# picoKey_230408.net
KiCad netlist of a schematic drawn in EAGLE
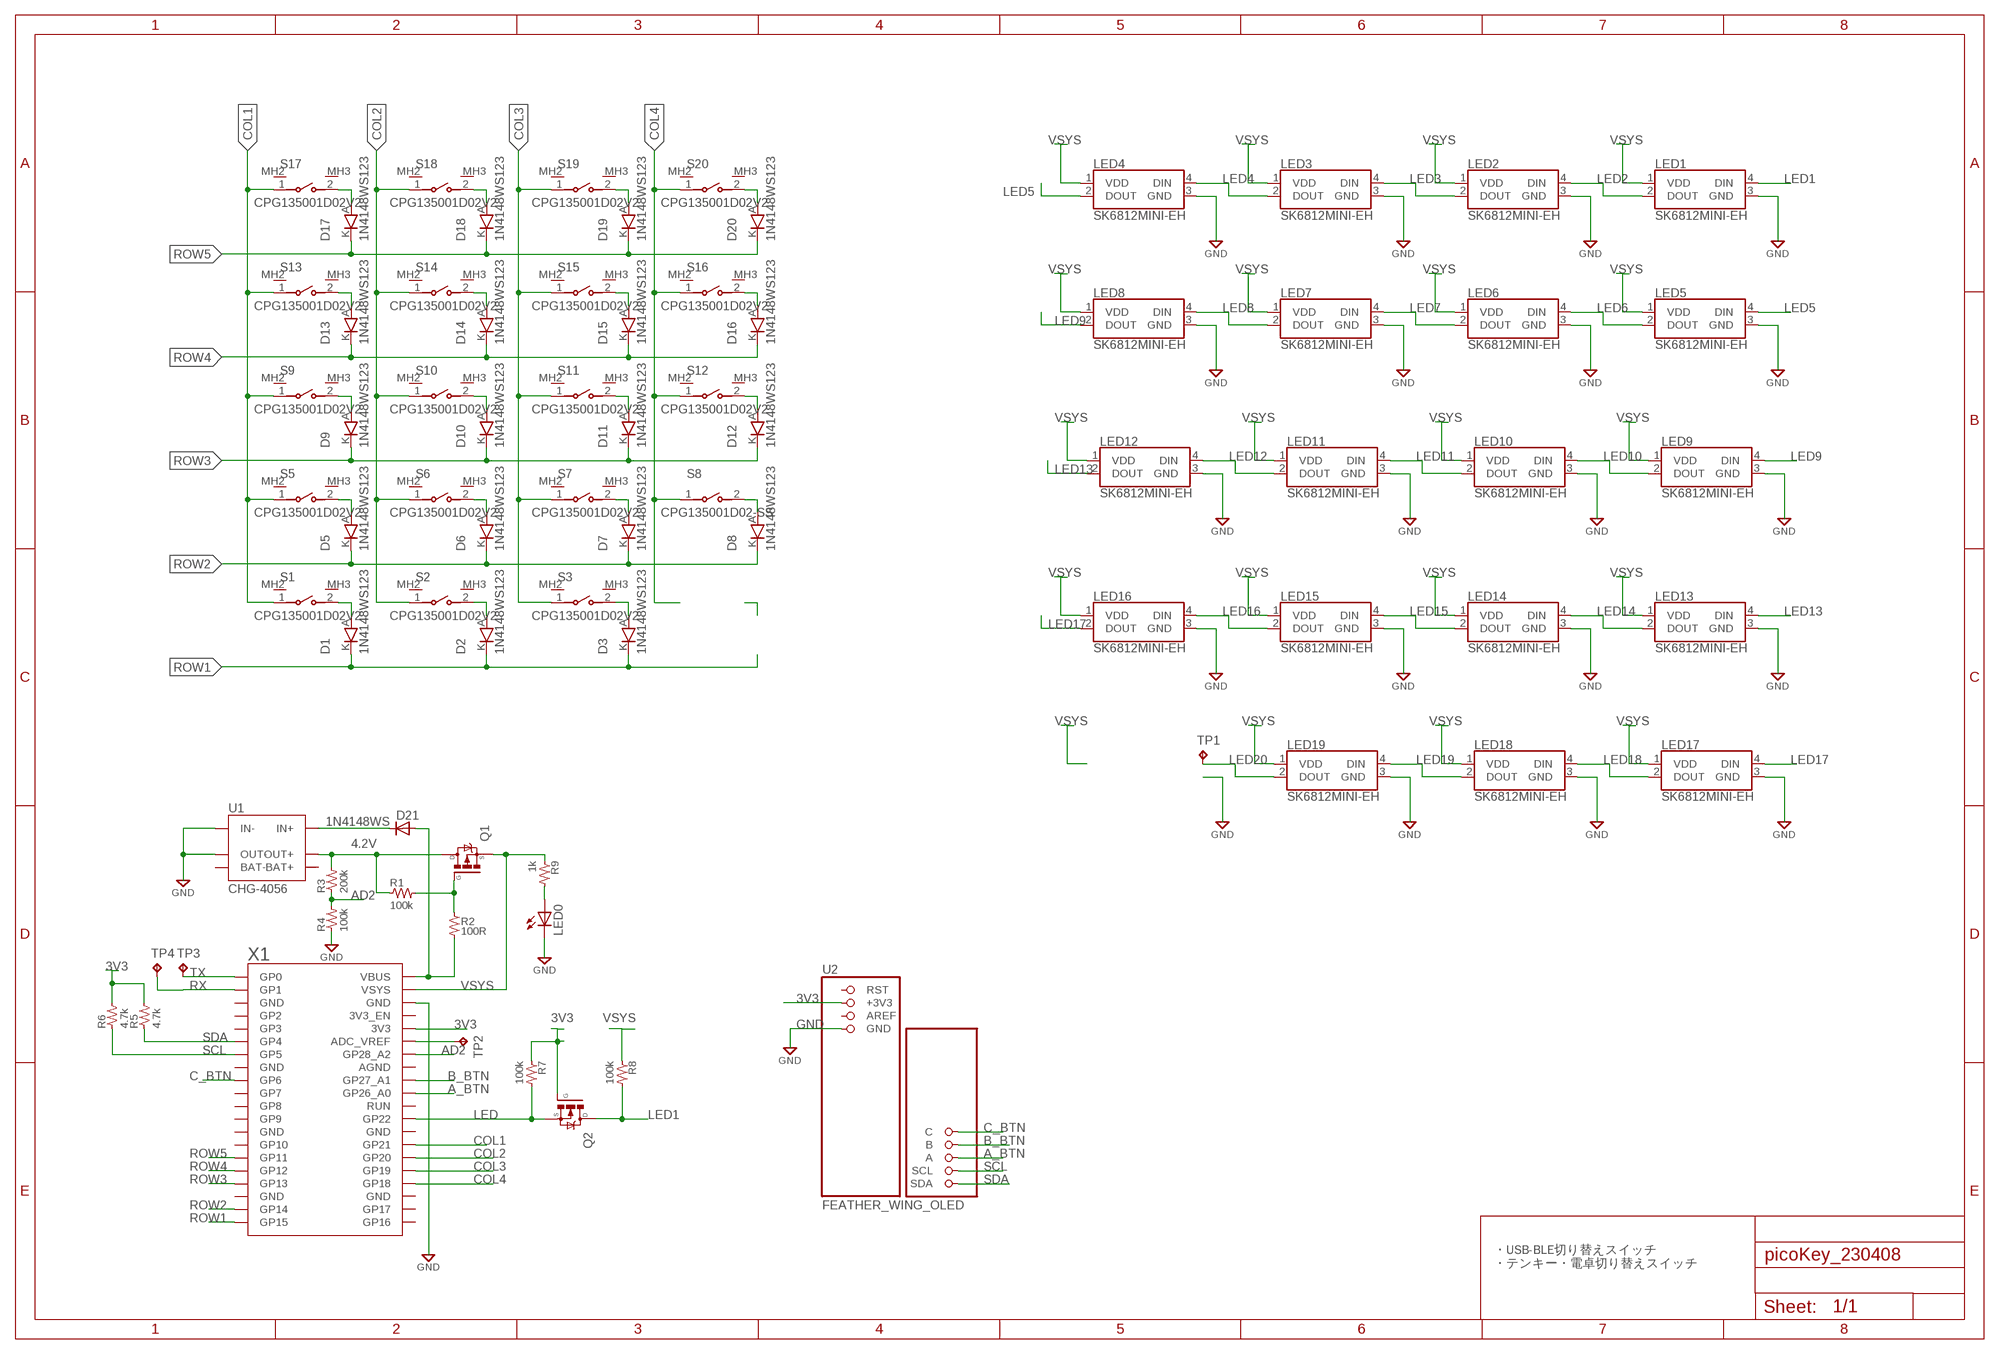
[diagram p0: schematic, sheet 1]

(export (version "E")
  (design (tool "Eeschema 10.0.6"))
  (components
    (comp (ref "D1")
      (value "1N4148WS123")
      (footprint "eagle-import:SOD-123")
      (libsource (lib "eagle-import") (part "1N4148WS123"))
    )
    (comp (ref "D2")
      (value "1N4148WS123")
      (footprint "eagle-import:SOD-123")
      (libsource (lib "eagle-import") (part "1N4148WS123"))
    )
    (comp (ref "D3")
      (value "1N4148WS123")
      (footprint "eagle-import:SOD-123")
      (libsource (lib "eagle-import") (part "1N4148WS123"))
    )
    (comp (ref "D5")
      (value "1N4148WS123")
      (footprint "eagle-import:SOD-123")
      (libsource (lib "eagle-import") (part "1N4148WS123"))
    )
    (comp (ref "D6")
      (value "1N4148WS123")
      (footprint "eagle-import:SOD-123")
      (libsource (lib "eagle-import") (part "1N4148WS123"))
    )
    (comp (ref "D7")
      (value "1N4148WS123")
      (footprint "eagle-import:SOD-123")
      (libsource (lib "eagle-import") (part "1N4148WS123"))
    )
    (comp (ref "D8")
      (value "1N4148WS123")
      (footprint "eagle-import:SOD-123")
      (libsource (lib "eagle-import") (part "1N4148WS123"))
    )
    (comp (ref "D9")
      (value "1N4148WS123")
      (footprint "eagle-import:SOD-123")
      (libsource (lib "eagle-import") (part "1N4148WS123"))
    )
    (comp (ref "D10")
      (value "1N4148WS123")
      (footprint "eagle-import:SOD-123")
      (libsource (lib "eagle-import") (part "1N4148WS123"))
    )
    (comp (ref "D11")
      (value "1N4148WS123")
      (footprint "eagle-import:SOD-123")
      (libsource (lib "eagle-import") (part "1N4148WS123"))
    )
    (comp (ref "D12")
      (value "1N4148WS123")
      (footprint "eagle-import:SOD-123")
      (libsource (lib "eagle-import") (part "1N4148WS123"))
    )
    (comp (ref "D13")
      (value "1N4148WS123")
      (footprint "eagle-import:SOD-123")
      (libsource (lib "eagle-import") (part "1N4148WS123"))
    )
    (comp (ref "D14")
      (value "1N4148WS123")
      (footprint "eagle-import:SOD-123")
      (libsource (lib "eagle-import") (part "1N4148WS123"))
    )
    (comp (ref "D15")
      (value "1N4148WS123")
      (footprint "eagle-import:SOD-123")
      (libsource (lib "eagle-import") (part "1N4148WS123"))
    )
    (comp (ref "D16")
      (value "1N4148WS123")
      (footprint "eagle-import:SOD-123")
      (libsource (lib "eagle-import") (part "1N4148WS123"))
    )
    (comp (ref "D17")
      (value "1N4148WS123")
      (footprint "eagle-import:SOD-123")
      (libsource (lib "eagle-import") (part "1N4148WS123"))
    )
    (comp (ref "D18")
      (value "1N4148WS123")
      (footprint "eagle-import:SOD-123")
      (libsource (lib "eagle-import") (part "1N4148WS123"))
    )
    (comp (ref "D19")
      (value "1N4148WS123")
      (footprint "eagle-import:SOD-123")
      (libsource (lib "eagle-import") (part "1N4148WS123"))
    )
    (comp (ref "D20")
      (value "1N4148WS123")
      (footprint "eagle-import:SOD-123")
      (libsource (lib "eagle-import") (part "1N4148WS123"))
    )
    (comp (ref "D21")
      (value "1N4148WS")
      (footprint "eagle-import:SOD-123")
      (libsource (lib "eagle-import") (part "DIODE123"))
    )
    (comp (ref "LED0")
      (value "LEDCHIP-LED0603")
      (footprint "eagle-import:CHIP-LED0603")
      (libsource (lib "eagle-import") (part "LEDCHIP-LED0603"))
    )
    (comp (ref "LED1")
      (value "SK6812MINI-EH")
      (footprint "eagle-import:SK6812MINIE-H")
      (libsource (lib "eagle-import") (part "SK6812MINI-EH"))
    )
    (comp (ref "LED2")
      (value "SK6812MINI-EH")
      (footprint "eagle-import:SK6812MINIE-H")
      (libsource (lib "eagle-import") (part "SK6812MINI-EH"))
    )
    (comp (ref "LED3")
      (value "SK6812MINI-EH")
      (footprint "eagle-import:SK6812MINIE-H")
      (libsource (lib "eagle-import") (part "SK6812MINI-EH"))
    )
    (comp (ref "LED4")
      (value "SK6812MINI-EH")
      (footprint "eagle-import:SK6812MINIE-H")
      (libsource (lib "eagle-import") (part "SK6812MINI-EH"))
    )
    (comp (ref "LED5")
      (value "SK6812MINI-EH")
      (footprint "eagle-import:SK6812MINIE-H")
      (libsource (lib "eagle-import") (part "SK6812MINI-EH"))
    )
    (comp (ref "LED6")
      (value "SK6812MINI-EH")
      (footprint "eagle-import:SK6812MINIE-H")
      (libsource (lib "eagle-import") (part "SK6812MINI-EH"))
    )
    (comp (ref "LED7")
      (value "SK6812MINI-EH")
      (footprint "eagle-import:SK6812MINIE-H")
      (libsource (lib "eagle-import") (part "SK6812MINI-EH"))
    )
    (comp (ref "LED8")
      (value "SK6812MINI-EH")
      (footprint "eagle-import:SK6812MINIE-H")
      (libsource (lib "eagle-import") (part "SK6812MINI-EH"))
    )
    (comp (ref "LED9")
      (value "SK6812MINI-EH")
      (footprint "eagle-import:SK6812MINIE-H")
      (libsource (lib "eagle-import") (part "SK6812MINI-EH"))
    )
    (comp (ref "LED10")
      (value "SK6812MINI-EH")
      (footprint "eagle-import:SK6812MINIE-H")
      (libsource (lib "eagle-import") (part "SK6812MINI-EH"))
    )
    (comp (ref "LED11")
      (value "SK6812MINI-EH")
      (footprint "eagle-import:SK6812MINIE-H")
      (libsource (lib "eagle-import") (part "SK6812MINI-EH"))
    )
    (comp (ref "LED12")
      (value "SK6812MINI-EH")
      (footprint "eagle-import:SK6812MINIE-H")
      (libsource (lib "eagle-import") (part "SK6812MINI-EH"))
    )
    (comp (ref "LED13")
      (value "SK6812MINI-EH")
      (footprint "eagle-import:SK6812MINIE-H")
      (libsource (lib "eagle-import") (part "SK6812MINI-EH"))
    )
    (comp (ref "LED14")
      (value "SK6812MINI-EH")
      (footprint "eagle-import:SK6812MINIE-H")
      (libsource (lib "eagle-import") (part "SK6812MINI-EH"))
    )
    (comp (ref "LED15")
      (value "SK6812MINI-EH")
      (footprint "eagle-import:SK6812MINIE-H")
      (libsource (lib "eagle-import") (part "SK6812MINI-EH"))
    )
    (comp (ref "LED16")
      (value "SK6812MINI-EH")
      (footprint "eagle-import:SK6812MINIE-H")
      (libsource (lib "eagle-import") (part "SK6812MINI-EH"))
    )
    (comp (ref "LED17")
      (value "SK6812MINI-EH")
      (footprint "eagle-import:SK6812MINIE-H")
      (libsource (lib "eagle-import") (part "SK6812MINI-EH"))
    )
    (comp (ref "LED18")
      (value "SK6812MINI-EH")
      (footprint "eagle-import:SK6812MINIE-H")
      (libsource (lib "eagle-import") (part "SK6812MINI-EH"))
    )
    (comp (ref "LED19")
      (value "SK6812MINI-EH")
      (footprint "eagle-import:SK6812MINIE-H")
      (libsource (lib "eagle-import") (part "SK6812MINI-EH"))
    )
    (comp (ref "Q1")
      (value "MOSFET-P")
      (footprint "eagle-import:SOT-23")
      (libsource (lib "eagle-import") (part "MOSFET-P"))
    )
    (comp (ref "Q2")
      (value "MOSFET-NSOT-23")
      (footprint "eagle-import:SOT-23")
      (libsource (lib "eagle-import") (part "MOSFET-NSOT-23"))
    )
    (comp (ref "R1")
      (value "100k")
      (footprint "eagle-import:R0603")
      (libsource (lib "eagle-import") (part "R_0603"))
    )
    (comp (ref "R2")
      (value "100R")
      (footprint "eagle-import:R0603")
      (libsource (lib "eagle-import") (part "R_0603"))
    )
    (comp (ref "R3")
      (value "200k")
      (footprint "eagle-import:R0603")
      (libsource (lib "eagle-import") (part "R_0603"))
    )
    (comp (ref "R4")
      (value "100k")
      (footprint "eagle-import:R0603")
      (libsource (lib "eagle-import") (part "R_0603"))
    )
    (comp (ref "R5")
      (value "4.7k")
      (footprint "eagle-import:R0603")
      (libsource (lib "eagle-import") (part "R_0603"))
    )
    (comp (ref "R6")
      (value "4.7k")
      (footprint "eagle-import:R0603")
      (libsource (lib "eagle-import") (part "R_0603"))
    )
    (comp (ref "R7")
      (value "100k")
      (footprint "eagle-import:R0603")
      (libsource (lib "eagle-import") (part "R_0603"))
    )
    (comp (ref "R8")
      (value "100k")
      (footprint "eagle-import:R0603")
      (libsource (lib "eagle-import") (part "R_0603"))
    )
    (comp (ref "R9")
      (value "1k")
      (footprint "eagle-import:R0603")
      (libsource (lib "eagle-import") (part "R_0603"))
    )
    (comp (ref "S1")
      (value "CPG135001D02V2")
      (footprint "eagle-import:KAILH_CHOC_V2")
      (libsource (lib "eagle-import") (part "CPG135001D02V2"))
    )
    (comp (ref "S2")
      (value "CPG135001D02V2")
      (footprint "eagle-import:KAILH_CHOC_V2")
      (libsource (lib "eagle-import") (part "CPG135001D02V2"))
    )
    (comp (ref "S3")
      (value "CPG135001D02V2")
      (footprint "eagle-import:KAILH_CHOC_V2")
      (libsource (lib "eagle-import") (part "CPG135001D02V2"))
    )
    (comp (ref "S5")
      (value "CPG135001D02V2")
      (footprint "eagle-import:KAILH_CHOC_V2")
      (libsource (lib "eagle-import") (part "CPG135001D02V2"))
    )
    (comp (ref "S6")
      (value "CPG135001D02V2")
      (footprint "eagle-import:KAILH_CHOC_V2")
      (libsource (lib "eagle-import") (part "CPG135001D02V2"))
    )
    (comp (ref "S7")
      (value "CPG135001D02V2")
      (footprint "eagle-import:KAILH_CHOC_V2")
      (libsource (lib "eagle-import") (part "CPG135001D02V2"))
    )
    (comp (ref "S8")
      (value "CPG135001D02-SS")
      (footprint "eagle-import:CPG135001D02-S")
      (libsource (lib "eagle-import") (part "CPG135001D02-SS"))
    )
    (comp (ref "S9")
      (value "CPG135001D02V2")
      (footprint "eagle-import:KAILH_CHOC_V2")
      (libsource (lib "eagle-import") (part "CPG135001D02V2"))
    )
    (comp (ref "S10")
      (value "CPG135001D02V2")
      (footprint "eagle-import:KAILH_CHOC_V2")
      (libsource (lib "eagle-import") (part "CPG135001D02V2"))
    )
    (comp (ref "S11")
      (value "CPG135001D02V2")
      (footprint "eagle-import:KAILH_CHOC_V2")
      (libsource (lib "eagle-import") (part "CPG135001D02V2"))
    )
    (comp (ref "S12")
      (value "CPG135001D02V2")
      (footprint "eagle-import:KAILH_CHOC_V2")
      (libsource (lib "eagle-import") (part "CPG135001D02V2"))
    )
    (comp (ref "S13")
      (value "CPG135001D02V2")
      (footprint "eagle-import:KAILH_CHOC_V2")
      (libsource (lib "eagle-import") (part "CPG135001D02V2"))
    )
    (comp (ref "S14")
      (value "CPG135001D02V2")
      (footprint "eagle-import:KAILH_CHOC_V2")
      (libsource (lib "eagle-import") (part "CPG135001D02V2"))
    )
    (comp (ref "S15")
      (value "CPG135001D02V2")
      (footprint "eagle-import:KAILH_CHOC_V2")
      (libsource (lib "eagle-import") (part "CPG135001D02V2"))
    )
    (comp (ref "S16")
      (value "CPG135001D02V2")
      (footprint "eagle-import:KAILH_CHOC_V2")
      (libsource (lib "eagle-import") (part "CPG135001D02V2"))
    )
    (comp (ref "S17")
      (value "CPG135001D02V2")
      (footprint "eagle-import:KAILH_CHOC_V2")
      (libsource (lib "eagle-import") (part "CPG135001D02V2"))
    )
    (comp (ref "S18")
      (value "CPG135001D02V2")
      (footprint "eagle-import:KAILH_CHOC_V2")
      (libsource (lib "eagle-import") (part "CPG135001D02V2"))
    )
    (comp (ref "S19")
      (value "CPG135001D02V2")
      (footprint "eagle-import:KAILH_CHOC_V2")
      (libsource (lib "eagle-import") (part "CPG135001D02V2"))
    )
    (comp (ref "S20")
      (value "CPG135001D02V2")
      (footprint "eagle-import:KAILH_CHOC_V2")
      (libsource (lib "eagle-import") (part "CPG135001D02V2"))
    )
    (comp (ref "TP1")
      (value "TPTP06R")
      (footprint "eagle-import:TP06R")
      (libsource (lib "eagle-import") (part "TPTP06R"))
    )
    (comp (ref "TP2")
      (value "TPTP06R")
      (footprint "eagle-import:TP06R")
      (libsource (lib "eagle-import") (part "TPTP06R"))
    )
    (comp (ref "TP3")
      (value "TPTP06R")
      (footprint "eagle-import:TP06R")
      (libsource (lib "eagle-import") (part "TPTP06R"))
    )
    (comp (ref "TP4")
      (value "TPTP06R")
      (footprint "eagle-import:TP06R")
      (libsource (lib "eagle-import") (part "TPTP06R"))
    )
    (comp (ref "U1")
      (value "CHG-4056")
      (footprint "eagle-import:CHG-4056")
      (libsource (lib "eagle-import") (part "CHG-4056"))
    )
    (comp (ref "U2")
      (value "FEATHER_WING_OLED")
      (footprint "eagle-import:FEATHER_WING_OLED")
      (libsource (lib "eagle-import") (part "FEATHER_WING_OLED"))
    )
    (comp (ref "X1")
      (value "RASPBERRYPI_PICO_RPI_PICO_MY-MY")
      (footprint "eagle-import:RASPBERRYPI_PICO_RPI_PICO_MY")
      (libsource (lib "eagle-import") (part "RASPBERRYPI_PICO_RPI_PICO_MY-MY"))
    )
  )
  (nets
    (net (code "1") (name "/3V3") (class "Default")
      (node (ref "Q2") (pin "3") (pinfunction "G_3") (pintype "passive"))
      (node (ref "R5") (pin "2") (pinfunction "2_2") (pintype "passive"))
      (node (ref "R6") (pin "2") (pinfunction "2_2") (pintype "passive"))
      (node (ref "R7") (pin "1") (pinfunction "1_1") (pintype "passive"))
      (node (ref "U2") (pin "15") (pinfunction "+3V3_15") (pintype "passive"))
      (node (ref "X1") (pin "3V3") (pinfunction "3V3_3V3") (pintype "bidirectional"))
    )
    (net (code "2") (name "/4.2V") (class "Default")
      (node (ref "Q1") (pin "2") (pinfunction "D_2") (pintype "passive"))
      (node (ref "R1") (pin "1") (pinfunction "1_1") (pintype "passive"))
      (node (ref "R3") (pin "2") (pinfunction "2_2") (pintype "passive"))
      (node (ref "U1") (pin "OUT+") (pinfunction "OUT+_OUT+") (pintype "bidirectional"))
    )
    (net (code "3") (name "/AD2") (class "Default")
      (node (ref "R3") (pin "1") (pinfunction "1_1") (pintype "passive"))
      (node (ref "R4") (pin "2") (pinfunction "2_2") (pintype "passive"))
      (node (ref "X1") (pin "GP28_A2") (pinfunction "GP28_A2_GP28_A2") (pintype "bidirectional"))
    )
    (net (code "4") (name "/A_BTN") (class "Default")
      (node (ref "U2") (pin "26") (pinfunction "A_26") (pintype "passive"))
      (node (ref "X1") (pin "GP26_A0") (pinfunction "GP26_A0_GP26_A0") (pintype "bidirectional"))
    )
    (net (code "5") (name "/B_BTN") (class "Default")
      (node (ref "U2") (pin "25") (pinfunction "B_25") (pintype "passive"))
      (node (ref "X1") (pin "GP27_A1") (pinfunction "GP27_A1_GP27_A1") (pintype "bidirectional"))
    )
    (net (code "6") (name "/C_BTN") (class "Default")
      (node (ref "U2") (pin "24") (pinfunction "C_24") (pintype "passive"))
      (node (ref "X1") (pin "GP6") (pinfunction "GP6_GP6") (pintype "bidirectional"))
    )
    (net (code "7") (name "/LED") (class "Default")
      (node (ref "Q2") (pin "1") (pinfunction "S_1") (pintype "passive"))
      (node (ref "R7") (pin "2") (pinfunction "2_2") (pintype "passive"))
      (node (ref "X1") (pin "GP22") (pinfunction "GP22_GP22") (pintype "bidirectional"))
    )
    (net (code "8") (name "/LED1") (class "Default")
      (node (ref "LED1") (pin "4") (pinfunction "DIN_4") (pintype "bidirectional"))
      (node (ref "Q2") (pin "2") (pinfunction "D_2") (pintype "passive"))
      (node (ref "R8") (pin "2") (pinfunction "2_2") (pintype "passive"))
    )
    (net (code "9") (name "/LED2") (class "Default")
      (node (ref "LED1") (pin "2") (pinfunction "DOUT_2") (pintype "bidirectional"))
      (node (ref "LED2") (pin "4") (pinfunction "DIN_4") (pintype "bidirectional"))
    )
    (net (code "10") (name "/LED3") (class "Default")
      (node (ref "LED2") (pin "2") (pinfunction "DOUT_2") (pintype "bidirectional"))
      (node (ref "LED3") (pin "4") (pinfunction "DIN_4") (pintype "bidirectional"))
    )
    (net (code "11") (name "/LED4") (class "Default")
      (node (ref "LED3") (pin "2") (pinfunction "DOUT_2") (pintype "bidirectional"))
      (node (ref "LED4") (pin "4") (pinfunction "DIN_4") (pintype "bidirectional"))
    )
    (net (code "12") (name "/LED5") (class "Default")
      (node (ref "LED4") (pin "2") (pinfunction "DOUT_2") (pintype "bidirectional"))
      (node (ref "LED5") (pin "4") (pinfunction "DIN_4") (pintype "bidirectional"))
    )
    (net (code "13") (name "/LED6") (class "Default")
      (node (ref "LED5") (pin "2") (pinfunction "DOUT_2") (pintype "bidirectional"))
      (node (ref "LED6") (pin "4") (pinfunction "DIN_4") (pintype "bidirectional"))
    )
    (net (code "14") (name "/LED7") (class "Default")
      (node (ref "LED6") (pin "2") (pinfunction "DOUT_2") (pintype "bidirectional"))
      (node (ref "LED7") (pin "4") (pinfunction "DIN_4") (pintype "bidirectional"))
    )
    (net (code "15") (name "/LED8") (class "Default")
      (node (ref "LED7") (pin "2") (pinfunction "DOUT_2") (pintype "bidirectional"))
      (node (ref "LED8") (pin "4") (pinfunction "DIN_4") (pintype "bidirectional"))
    )
    (net (code "16") (name "/LED9") (class "Default")
      (node (ref "LED8") (pin "2") (pinfunction "DOUT_2") (pintype "bidirectional"))
      (node (ref "LED9") (pin "4") (pinfunction "DIN_4") (pintype "bidirectional"))
    )
    (net (code "17") (name "/LED10") (class "Default")
      (node (ref "LED10") (pin "4") (pinfunction "DIN_4") (pintype "bidirectional"))
      (node (ref "LED9") (pin "2") (pinfunction "DOUT_2") (pintype "bidirectional"))
    )
    (net (code "18") (name "/LED11") (class "Default")
      (node (ref "LED10") (pin "2") (pinfunction "DOUT_2") (pintype "bidirectional"))
      (node (ref "LED11") (pin "4") (pinfunction "DIN_4") (pintype "bidirectional"))
    )
    (net (code "19") (name "/LED12") (class "Default")
      (node (ref "LED11") (pin "2") (pinfunction "DOUT_2") (pintype "bidirectional"))
      (node (ref "LED12") (pin "4") (pinfunction "DIN_4") (pintype "bidirectional"))
    )
    (net (code "20") (name "/LED13") (class "Default")
      (node (ref "LED12") (pin "2") (pinfunction "DOUT_2") (pintype "bidirectional"))
      (node (ref "LED13") (pin "4") (pinfunction "DIN_4") (pintype "bidirectional"))
    )
    (net (code "21") (name "/LED14") (class "Default")
      (node (ref "LED13") (pin "2") (pinfunction "DOUT_2") (pintype "bidirectional"))
      (node (ref "LED14") (pin "4") (pinfunction "DIN_4") (pintype "bidirectional"))
    )
    (net (code "22") (name "/LED15") (class "Default")
      (node (ref "LED14") (pin "2") (pinfunction "DOUT_2") (pintype "bidirectional"))
      (node (ref "LED15") (pin "4") (pinfunction "DIN_4") (pintype "bidirectional"))
    )
    (net (code "23") (name "/LED16") (class "Default")
      (node (ref "LED15") (pin "2") (pinfunction "DOUT_2") (pintype "bidirectional"))
      (node (ref "LED16") (pin "4") (pinfunction "DIN_4") (pintype "bidirectional"))
    )
    (net (code "24") (name "/LED17") (class "Default")
      (node (ref "LED16") (pin "2") (pinfunction "DOUT_2") (pintype "bidirectional"))
      (node (ref "LED17") (pin "4") (pinfunction "DIN_4") (pintype "bidirectional"))
    )
    (net (code "25") (name "/LED18") (class "Default")
      (node (ref "LED17") (pin "2") (pinfunction "DOUT_2") (pintype "bidirectional"))
      (node (ref "LED18") (pin "4") (pinfunction "DIN_4") (pintype "bidirectional"))
    )
    (net (code "26") (name "/LED19") (class "Default")
      (node (ref "LED18") (pin "2") (pinfunction "DOUT_2") (pintype "bidirectional"))
      (node (ref "LED19") (pin "4") (pinfunction "DIN_4") (pintype "bidirectional"))
    )
    (net (code "27") (name "/LED20") (class "Default")
      (node (ref "LED19") (pin "2") (pinfunction "DOUT_2") (pintype "bidirectional"))
      (node (ref "TP1") (pin "TP") (pinfunction "TP_TP") (pintype "input"))
    )
    (net (code "28") (name "/RX") (class "Default")
      (node (ref "TP4") (pin "TP") (pinfunction "TP_TP") (pintype "input"))
      (node (ref "X1") (pin "GP1") (pinfunction "GP1_GP1") (pintype "bidirectional"))
    )
    (net (code "29") (name "/SCL") (class "Default")
      (node (ref "R6") (pin "1") (pinfunction "1_1") (pintype "passive"))
      (node (ref "U2") (pin "27") (pinfunction "SCL_27") (pintype "passive"))
      (node (ref "X1") (pin "GP5") (pinfunction "GP5_GP5") (pintype "bidirectional"))
    )
    (net (code "30") (name "/SDA") (class "Default")
      (node (ref "R5") (pin "1") (pinfunction "1_1") (pintype "passive"))
      (node (ref "U2") (pin "28") (pinfunction "SDA_28") (pintype "passive"))
      (node (ref "X1") (pin "GP4") (pinfunction "GP4_GP4") (pintype "bidirectional"))
    )
    (net (code "31") (name "/TX") (class "Default")
      (node (ref "TP3") (pin "TP") (pinfunction "TP_TP") (pintype "input"))
      (node (ref "X1") (pin "GP0") (pinfunction "GP0_GP0") (pintype "bidirectional"))
    )
    (net (code "32") (name "/VSYS") (class "Default")
      (node (ref "LED1") (pin "1") (pinfunction "VDD_1") (pintype "bidirectional"))
      (node (ref "LED10") (pin "1") (pinfunction "VDD_1") (pintype "bidirectional"))
      (node (ref "LED11") (pin "1") (pinfunction "VDD_1") (pintype "bidirectional"))
      (node (ref "LED12") (pin "1") (pinfunction "VDD_1") (pintype "bidirectional"))
      (node (ref "LED13") (pin "1") (pinfunction "VDD_1") (pintype "bidirectional"))
      (node (ref "LED14") (pin "1") (pinfunction "VDD_1") (pintype "bidirectional"))
      (node (ref "LED15") (pin "1") (pinfunction "VDD_1") (pintype "bidirectional"))
      (node (ref "LED16") (pin "1") (pinfunction "VDD_1") (pintype "bidirectional"))
      (node (ref "LED17") (pin "1") (pinfunction "VDD_1") (pintype "bidirectional"))
      (node (ref "LED18") (pin "1") (pinfunction "VDD_1") (pintype "bidirectional"))
      (node (ref "LED19") (pin "1") (pinfunction "VDD_1") (pintype "bidirectional"))
      (node (ref "LED2") (pin "1") (pinfunction "VDD_1") (pintype "bidirectional"))
      (node (ref "LED3") (pin "1") (pinfunction "VDD_1") (pintype "bidirectional"))
      (node (ref "LED4") (pin "1") (pinfunction "VDD_1") (pintype "bidirectional"))
      (node (ref "LED5") (pin "1") (pinfunction "VDD_1") (pintype "bidirectional"))
      (node (ref "LED6") (pin "1") (pinfunction "VDD_1") (pintype "bidirectional"))
      (node (ref "LED7") (pin "1") (pinfunction "VDD_1") (pintype "bidirectional"))
      (node (ref "LED8") (pin "1") (pinfunction "VDD_1") (pintype "bidirectional"))
      (node (ref "LED9") (pin "1") (pinfunction "VDD_1") (pintype "bidirectional"))
      (node (ref "Q1") (pin "1") (pinfunction "S_1") (pintype "passive"))
      (node (ref "R8") (pin "1") (pinfunction "1_1") (pintype "passive"))
      (node (ref "R9") (pin "1") (pinfunction "1_1") (pintype "passive"))
      (node (ref "X1") (pin "VSYS") (pinfunction "VSYS_VSYS") (pintype "bidirectional"))
    )
    (net (code "33") (name "COL1") (class "Default")
      (node (ref "S1") (pin "1") (pinfunction "1_1") (pintype "bidirectional"))
      (node (ref "S13") (pin "1") (pinfunction "1_1") (pintype "bidirectional"))
      (node (ref "S17") (pin "1") (pinfunction "1_1") (pintype "bidirectional"))
      (node (ref "S5") (pin "1") (pinfunction "1_1") (pintype "bidirectional"))
      (node (ref "S9") (pin "1") (pinfunction "1_1") (pintype "bidirectional"))
      (node (ref "X1") (pin "GP21") (pinfunction "GP21_GP21") (pintype "bidirectional"))
    )
    (net (code "34") (name "COL2") (class "Default")
      (node (ref "S10") (pin "1") (pinfunction "1_1") (pintype "bidirectional"))
      (node (ref "S14") (pin "1") (pinfunction "1_1") (pintype "bidirectional"))
      (node (ref "S18") (pin "1") (pinfunction "1_1") (pintype "bidirectional"))
      (node (ref "S2") (pin "1") (pinfunction "1_1") (pintype "bidirectional"))
      (node (ref "S6") (pin "1") (pinfunction "1_1") (pintype "bidirectional"))
      (node (ref "X1") (pin "GP20") (pinfunction "GP20_GP20") (pintype "bidirectional"))
    )
    (net (code "35") (name "COL3") (class "Default")
      (node (ref "S11") (pin "1") (pinfunction "1_1") (pintype "bidirectional"))
      (node (ref "S15") (pin "1") (pinfunction "1_1") (pintype "bidirectional"))
      (node (ref "S19") (pin "1") (pinfunction "1_1") (pintype "bidirectional"))
      (node (ref "S3") (pin "1") (pinfunction "1_1") (pintype "bidirectional"))
      (node (ref "S7") (pin "1") (pinfunction "1_1") (pintype "bidirectional"))
      (node (ref "X1") (pin "GP19") (pinfunction "GP19_GP19") (pintype "bidirectional"))
    )
    (net (code "36") (name "COL4") (class "Default")
      (node (ref "S12") (pin "1") (pinfunction "1_1") (pintype "bidirectional"))
      (node (ref "S16") (pin "1") (pinfunction "1_1") (pintype "bidirectional"))
      (node (ref "S20") (pin "1") (pinfunction "1_1") (pintype "bidirectional"))
      (node (ref "S8") (pin "1") (pinfunction "1_1") (pintype "bidirectional"))
      (node (ref "X1") (pin "GP18") (pinfunction "GP18_GP18") (pintype "bidirectional"))
    )
    (net (code "37") (name "G") (class "Default")
      (node (ref "LED0") (pin "C") (pinfunction "C_C") (pintype "passive"))
      (node (ref "LED1") (pin "3") (pinfunction "GND_3") (pintype "bidirectional"))
      (node (ref "LED10") (pin "3") (pinfunction "GND_3") (pintype "bidirectional"))
      (node (ref "LED11") (pin "3") (pinfunction "GND_3") (pintype "bidirectional"))
      (node (ref "LED12") (pin "3") (pinfunction "GND_3") (pintype "bidirectional"))
      (node (ref "LED13") (pin "3") (pinfunction "GND_3") (pintype "bidirectional"))
      (node (ref "LED14") (pin "3") (pinfunction "GND_3") (pintype "bidirectional"))
      (node (ref "LED15") (pin "3") (pinfunction "GND_3") (pintype "bidirectional"))
      (node (ref "LED16") (pin "3") (pinfunction "GND_3") (pintype "bidirectional"))
      (node (ref "LED17") (pin "3") (pinfunction "GND_3") (pintype "bidirectional"))
      (node (ref "LED18") (pin "3") (pinfunction "GND_3") (pintype "bidirectional"))
      (node (ref "LED19") (pin "3") (pinfunction "GND_3") (pintype "bidirectional"))
      (node (ref "LED2") (pin "3") (pinfunction "GND_3") (pintype "bidirectional"))
      (node (ref "LED3") (pin "3") (pinfunction "GND_3") (pintype "bidirectional"))
      (node (ref "LED4") (pin "3") (pinfunction "GND_3") (pintype "bidirectional"))
      (node (ref "LED5") (pin "3") (pinfunction "GND_3") (pintype "bidirectional"))
      (node (ref "LED6") (pin "3") (pinfunction "GND_3") (pintype "bidirectional"))
      (node (ref "LED7") (pin "3") (pinfunction "GND_3") (pintype "bidirectional"))
      (node (ref "LED8") (pin "3") (pinfunction "GND_3") (pintype "bidirectional"))
      (node (ref "LED9") (pin "3") (pinfunction "GND_3") (pintype "bidirectional"))
      (node (ref "R4") (pin "1") (pinfunction "1_1") (pintype "passive"))
      (node (ref "U1") (pin "IN-") (pinfunction "IN-_IN-") (pintype "bidirectional"))
      (node (ref "U1") (pin "OUT-") (pinfunction "OUT-_OUT-") (pintype "bidirectional"))
      (node (ref "U2") (pin "13") (pinfunction "GND_13") (pintype "passive"))
      (node (ref "X1") (pin "GND@8") (pinfunction "GND_GND@8") (pintype "bidirectional"))
    )
    (net (code "38") (name "Net-(D1-PadA)") (class "Default")
      (node (ref "D1") (pin "A") (pinfunction "A_A") (pintype "bidirectional"))
      (node (ref "S1") (pin "2") (pinfunction "2_2") (pintype "bidirectional"))
    )
    (net (code "39") (name "Net-(D2-PadA)") (class "Default")
      (node (ref "D2") (pin "A") (pinfunction "A_A") (pintype "bidirectional"))
      (node (ref "S2") (pin "2") (pinfunction "2_2") (pintype "bidirectional"))
    )
    (net (code "40") (name "Net-(D3-PadA)") (class "Default")
      (node (ref "D3") (pin "A") (pinfunction "A_A") (pintype "bidirectional"))
      (node (ref "S3") (pin "2") (pinfunction "2_2") (pintype "bidirectional"))
    )
    (net (code "41") (name "Net-(D5-PadA)") (class "Default")
      (node (ref "D5") (pin "A") (pinfunction "A_A") (pintype "bidirectional"))
      (node (ref "S5") (pin "2") (pinfunction "2_2") (pintype "bidirectional"))
    )
    (net (code "42") (name "Net-(D6-PadA)") (class "Default")
      (node (ref "D6") (pin "A") (pinfunction "A_A") (pintype "bidirectional"))
      (node (ref "S6") (pin "2") (pinfunction "2_2") (pintype "bidirectional"))
    )
    (net (code "43") (name "Net-(D7-PadA)") (class "Default")
      (node (ref "D7") (pin "A") (pinfunction "A_A") (pintype "bidirectional"))
      (node (ref "S7") (pin "2") (pinfunction "2_2") (pintype "bidirectional"))
    )
    (net (code "44") (name "Net-(D8-PadA)") (class "Default")
      (node (ref "D8") (pin "A") (pinfunction "A_A") (pintype "bidirectional"))
      (node (ref "S8") (pin "2") (pinfunction "2_2") (pintype "bidirectional"))
    )
    (net (code "45") (name "Net-(D9-PadA)") (class "Default")
      (node (ref "D9") (pin "A") (pinfunction "A_A") (pintype "bidirectional"))
      (node (ref "S9") (pin "2") (pinfunction "2_2") (pintype "bidirectional"))
    )
    (net (code "46") (name "Net-(D10-PadA)") (class "Default")
      (node (ref "D10") (pin "A") (pinfunction "A_A") (pintype "bidirectional"))
      (node (ref "S10") (pin "2") (pinfunction "2_2") (pintype "bidirectional"))
    )
    (net (code "47") (name "Net-(D11-PadA)") (class "Default")
      (node (ref "D11") (pin "A") (pinfunction "A_A") (pintype "bidirectional"))
      (node (ref "S11") (pin "2") (pinfunction "2_2") (pintype "bidirectional"))
    )
    (net (code "48") (name "Net-(D12-PadA)") (class "Default")
      (node (ref "D12") (pin "A") (pinfunction "A_A") (pintype "bidirectional"))
      (node (ref "S12") (pin "2") (pinfunction "2_2") (pintype "bidirectional"))
    )
    (net (code "49") (name "Net-(D13-PadA)") (class "Default")
      (node (ref "D13") (pin "A") (pinfunction "A_A") (pintype "bidirectional"))
      (node (ref "S13") (pin "2") (pinfunction "2_2") (pintype "bidirectional"))
    )
    (net (code "50") (name "Net-(D14-PadA)") (class "Default")
      (node (ref "D14") (pin "A") (pinfunction "A_A") (pintype "bidirectional"))
      (node (ref "S14") (pin "2") (pinfunction "2_2") (pintype "bidirectional"))
    )
    (net (code "51") (name "Net-(D15-PadA)") (class "Default")
      (node (ref "D15") (pin "A") (pinfunction "A_A") (pintype "bidirectional"))
      (node (ref "S15") (pin "2") (pinfunction "2_2") (pintype "bidirectional"))
    )
    (net (code "52") (name "Net-(D16-PadA)") (class "Default")
      (node (ref "D16") (pin "A") (pinfunction "A_A") (pintype "bidirectional"))
      (node (ref "S16") (pin "2") (pinfunction "2_2") (pintype "bidirectional"))
    )
    (net (code "53") (name "Net-(D17-PadA)") (class "Default")
      (node (ref "D17") (pin "A") (pinfunction "A_A") (pintype "bidirectional"))
      (node (ref "S17") (pin "2") (pinfunction "2_2") (pintype "bidirectional"))
    )
    (net (code "54") (name "Net-(D18-PadA)") (class "Default")
      (node (ref "D18") (pin "A") (pinfunction "A_A") (pintype "bidirectional"))
      (node (ref "S18") (pin "2") (pinfunction "2_2") (pintype "bidirectional"))
    )
    (net (code "55") (name "Net-(D19-PadA)") (class "Default")
      (node (ref "D19") (pin "A") (pinfunction "A_A") (pintype "bidirectional"))
      (node (ref "S19") (pin "2") (pinfunction "2_2") (pintype "bidirectional"))
    )
    (net (code "56") (name "Net-(D20-PadA)") (class "Default")
      (node (ref "D20") (pin "A") (pinfunction "A_A") (pintype "bidirectional"))
      (node (ref "S20") (pin "2") (pinfunction "2_2") (pintype "bidirectional"))
    )
    (net (code "57") (name "Net-(D21-C)") (class "Default")
      (node (ref "D21") (pin "K") (pinfunction "C_K") (pintype "passive"))
      (node (ref "U1") (pin "IN+") (pinfunction "IN+_IN+") (pintype "bidirectional"))
    )
    (net (code "58") (name "Net-(D21-PadA)") (class "Default")
      (node (ref "D21") (pin "A") (pinfunction "A_A") (pintype "passive"))
      (node (ref "R2") (pin "2") (pinfunction "2_2") (pintype "passive"))
      (node (ref "X1") (pin "VBUS") (pinfunction "VBUS_VBUS") (pintype "bidirectional"))
    )
    (net (code "59") (name "Net-(LED0-PadA)") (class "Default")
      (node (ref "LED0") (pin "A") (pinfunction "A_A") (pintype "passive"))
      (node (ref "R9") (pin "2") (pinfunction "2_2") (pintype "passive"))
    )
    (net (code "60") (name "Net-(Q1-G)") (class "Default")
      (node (ref "Q1") (pin "3") (pinfunction "G_3") (pintype "passive"))
      (node (ref "R1") (pin "2") (pinfunction "2_2") (pintype "passive"))
      (node (ref "R2") (pin "1") (pinfunction "1_1") (pintype "passive"))
    )
    (net (code "61") (name "Net-(TP2-PadTP)") (class "Default")
      (node (ref "TP2") (pin "TP") (pinfunction "TP_TP") (pintype "input"))
      (node (ref "X1") (pin "ADC_VREF") (pinfunction "ADC_VREF_ADC_VREF") (pintype "bidirectional"))
    )
    (net (code "62") (name "ROW1") (class "Default")
      (node (ref "D1") (pin "K") (pinfunction "K_K") (pintype "bidirectional"))
      (node (ref "D2") (pin "K") (pinfunction "K_K") (pintype "bidirectional"))
      (node (ref "D3") (pin "K") (pinfunction "K_K") (pintype "bidirectional"))
      (node (ref "X1") (pin "GP15") (pinfunction "GP15_GP15") (pintype "bidirectional"))
    )
    (net (code "63") (name "ROW2") (class "Default")
      (node (ref "D5") (pin "K") (pinfunction "K_K") (pintype "bidirectional"))
      (node (ref "D6") (pin "K") (pinfunction "K_K") (pintype "bidirectional"))
      (node (ref "D7") (pin "K") (pinfunction "K_K") (pintype "bidirectional"))
      (node (ref "D8") (pin "K") (pinfunction "K_K") (pintype "bidirectional"))
      (node (ref "X1") (pin "GP14") (pinfunction "GP14_GP14") (pintype "bidirectional"))
    )
    (net (code "64") (name "ROW3") (class "Default")
      (node (ref "D10") (pin "K") (pinfunction "K_K") (pintype "bidirectional"))
      (node (ref "D11") (pin "K") (pinfunction "K_K") (pintype "bidirectional"))
      (node (ref "D12") (pin "K") (pinfunction "K_K") (pintype "bidirectional"))
      (node (ref "D9") (pin "K") (pinfunction "K_K") (pintype "bidirectional"))
      (node (ref "X1") (pin "GP13") (pinfunction "GP13_GP13") (pintype "bidirectional"))
    )
    (net (code "65") (name "ROW4") (class "Default")
      (node (ref "D13") (pin "K") (pinfunction "K_K") (pintype "bidirectional"))
      (node (ref "D14") (pin "K") (pinfunction "K_K") (pintype "bidirectional"))
      (node (ref "D15") (pin "K") (pinfunction "K_K") (pintype "bidirectional"))
      (node (ref "D16") (pin "K") (pinfunction "K_K") (pintype "bidirectional"))
      (node (ref "X1") (pin "GP12") (pinfunction "GP12_GP12") (pintype "bidirectional"))
    )
    (net (code "66") (name "ROW5") (class "Default")
      (node (ref "D17") (pin "K") (pinfunction "K_K") (pintype "bidirectional"))
      (node (ref "D18") (pin "K") (pinfunction "K_K") (pintype "bidirectional"))
      (node (ref "D19") (pin "K") (pinfunction "K_K") (pintype "bidirectional"))
      (node (ref "D20") (pin "K") (pinfunction "K_K") (pintype "bidirectional"))
      (node (ref "X1") (pin "GP11") (pinfunction "GP11_GP11") (pintype "bidirectional"))
    )
    (net (code "67") (name "unconnected-(S1-MH-PadMH2)") (class "Default")
      (node (ref "S1") (pin "MH2") (pinfunction "MH_MH2") (pintype "bidirectional"))
    )
    (net (code "68") (name "unconnected-(S1-MH-PadMH3)") (class "Default")
      (node (ref "S1") (pin "MH3") (pinfunction "MH_MH3") (pintype "bidirectional"))
    )
    (net (code "69") (name "unconnected-(S2-MH-PadMH2)") (class "Default")
      (node (ref "S2") (pin "MH2") (pinfunction "MH_MH2") (pintype "bidirectional"))
    )
    (net (code "70") (name "unconnected-(S2-MH-PadMH3)") (class "Default")
      (node (ref "S2") (pin "MH3") (pinfunction "MH_MH3") (pintype "bidirectional"))
    )
    (net (code "71") (name "unconnected-(S3-MH-PadMH2)") (class "Default")
      (node (ref "S3") (pin "MH2") (pinfunction "MH_MH2") (pintype "bidirectional"))
    )
    (net (code "72") (name "unconnected-(S3-MH-PadMH3)") (class "Default")
      (node (ref "S3") (pin "MH3") (pinfunction "MH_MH3") (pintype "bidirectional"))
    )
    (net (code "73") (name "unconnected-(S5-MH-PadMH2)") (class "Default")
      (node (ref "S5") (pin "MH2") (pinfunction "MH_MH2") (pintype "bidirectional"))
    )
    (net (code "74") (name "unconnected-(S5-MH-PadMH3)") (class "Default")
      (node (ref "S5") (pin "MH3") (pinfunction "MH_MH3") (pintype "bidirectional"))
    )
    (net (code "75") (name "unconnected-(S6-MH-PadMH2)") (class "Default")
      (node (ref "S6") (pin "MH2") (pinfunction "MH_MH2") (pintype "bidirectional"))
    )
    (net (code "76") (name "unconnected-(S6-MH-PadMH3)") (class "Default")
      (node (ref "S6") (pin "MH3") (pinfunction "MH_MH3") (pintype "bidirectional"))
    )
    (net (code "77") (name "unconnected-(S7-MH-PadMH2)") (class "Default")
      (node (ref "S7") (pin "MH2") (pinfunction "MH_MH2") (pintype "bidirectional"))
    )
    (net (code "78") (name "unconnected-(S7-MH-PadMH3)") (class "Default")
      (node (ref "S7") (pin "MH3") (pinfunction "MH_MH3") (pintype "bidirectional"))
    )
    (net (code "79") (name "unconnected-(S9-MH-PadMH2)") (class "Default")
      (node (ref "S9") (pin "MH2") (pinfunction "MH_MH2") (pintype "bidirectional"))
    )
    (net (code "80") (name "unconnected-(S9-MH-PadMH3)") (class "Default")
      (node (ref "S9") (pin "MH3") (pinfunction "MH_MH3") (pintype "bidirectional"))
    )
    (net (code "81") (name "unconnected-(S10-MH-PadMH2)") (class "Default")
      (node (ref "S10") (pin "MH2") (pinfunction "MH_MH2") (pintype "bidirectional"))
    )
    (net (code "82") (name "unconnected-(S10-MH-PadMH3)") (class "Default")
      (node (ref "S10") (pin "MH3") (pinfunction "MH_MH3") (pintype "bidirectional"))
    )
    (net (code "83") (name "unconnected-(S11-MH-PadMH2)") (class "Default")
      (node (ref "S11") (pin "MH2") (pinfunction "MH_MH2") (pintype "bidirectional"))
    )
    (net (code "84") (name "unconnected-(S11-MH-PadMH3)") (class "Default")
      (node (ref "S11") (pin "MH3") (pinfunction "MH_MH3") (pintype "bidirectional"))
    )
    (net (code "85") (name "unconnected-(S12-MH-PadMH2)") (class "Default")
      (node (ref "S12") (pin "MH2") (pinfunction "MH_MH2") (pintype "bidirectional"))
    )
    (net (code "86") (name "unconnected-(S12-MH-PadMH3)") (class "Default")
      (node (ref "S12") (pin "MH3") (pinfunction "MH_MH3") (pintype "bidirectional"))
    )
    (net (code "87") (name "unconnected-(S13-MH-PadMH2)") (class "Default")
      (node (ref "S13") (pin "MH2") (pinfunction "MH_MH2") (pintype "bidirectional"))
    )
    (net (code "88") (name "unconnected-(S13-MH-PadMH3)") (class "Default")
      (node (ref "S13") (pin "MH3") (pinfunction "MH_MH3") (pintype "bidirectional"))
    )
    (net (code "89") (name "unconnected-(S14-MH-PadMH2)") (class "Default")
      (node (ref "S14") (pin "MH2") (pinfunction "MH_MH2") (pintype "bidirectional"))
    )
    (net (code "90") (name "unconnected-(S14-MH-PadMH3)") (class "Default")
      (node (ref "S14") (pin "MH3") (pinfunction "MH_MH3") (pintype "bidirectional"))
    )
    (net (code "91") (name "unconnected-(S15-MH-PadMH2)") (class "Default")
      (node (ref "S15") (pin "MH2") (pinfunction "MH_MH2") (pintype "bidirectional"))
    )
    (net (code "92") (name "unconnected-(S15-MH-PadMH3)") (class "Default")
      (node (ref "S15") (pin "MH3") (pinfunction "MH_MH3") (pintype "bidirectional"))
    )
    (net (code "93") (name "unconnected-(S16-MH-PadMH2)") (class "Default")
      (node (ref "S16") (pin "MH2") (pinfunction "MH_MH2") (pintype "bidirectional"))
    )
    (net (code "94") (name "unconnected-(S16-MH-PadMH3)") (class "Default")
      (node (ref "S16") (pin "MH3") (pinfunction "MH_MH3") (pintype "bidirectional"))
    )
    (net (code "95") (name "unconnected-(S17-MH-PadMH2)") (class "Default")
      (node (ref "S17") (pin "MH2") (pinfunction "MH_MH2") (pintype "bidirectional"))
    )
    (net (code "96") (name "unconnected-(S17-MH-PadMH3)") (class "Default")
      (node (ref "S17") (pin "MH3") (pinfunction "MH_MH3") (pintype "bidirectional"))
    )
    (net (code "97") (name "unconnected-(S18-MH-PadMH2)") (class "Default")
      (node (ref "S18") (pin "MH2") (pinfunction "MH_MH2") (pintype "bidirectional"))
    )
    (net (code "98") (name "unconnected-(S18-MH-PadMH3)") (class "Default")
      (node (ref "S18") (pin "MH3") (pinfunction "MH_MH3") (pintype "bidirectional"))
    )
    (net (code "99") (name "unconnected-(S19-MH-PadMH2)") (class "Default")
      (node (ref "S19") (pin "MH2") (pinfunction "MH_MH2") (pintype "bidirectional"))
    )
    (net (code "100") (name "unconnected-(S19-MH-PadMH3)") (class "Default")
      (node (ref "S19") (pin "MH3") (pinfunction "MH_MH3") (pintype "bidirectional"))
    )
    (net (code "101") (name "unconnected-(S20-MH-PadMH2)") (class "Default")
      (node (ref "S20") (pin "MH2") (pinfunction "MH_MH2") (pintype "bidirectional"))
    )
    (net (code "102") (name "unconnected-(S20-MH-PadMH3)") (class "Default")
      (node (ref "S20") (pin "MH3") (pinfunction "MH_MH3") (pintype "bidirectional"))
    )
    (net (code "103") (name "unconnected-(U1-PadBAT+)") (class "Default")
      (node (ref "U1") (pin "BAT+") (pinfunction "BAT+_BAT+") (pintype "bidirectional"))
    )
    (net (code "104") (name "unconnected-(U1-PadBAT-)") (class "Default")
      (node (ref "U1") (pin "BAT-") (pinfunction "BAT-_BAT-") (pintype "bidirectional"))
    )
    (net (code "105") (name "unconnected-(U2-AREF-Pad14)") (class "Default")
      (node (ref "U2") (pin "14") (pinfunction "AREF_14") (pintype "passive"))
    )
    (net (code "106") (name "unconnected-(U2-RST-Pad16)") (class "Default")
      (node (ref "U2") (pin "16") (pinfunction "RST_16") (pintype "passive"))
    )
    (net (code "107") (name "unconnected-(X1-GND-PadGND@1)") (class "Default")
      (node (ref "X1") (pin "GND@1") (pinfunction "GND_GND@1") (pintype "bidirectional"))
    )
    (net (code "108") (name "unconnected-(X1-GND-PadGND@2)") (class "Default")
      (node (ref "X1") (pin "GND@2") (pinfunction "GND_GND@2") (pintype "bidirectional"))
    )
    (net (code "109") (name "unconnected-(X1-GND-PadGND@3)") (class "Default")
      (node (ref "X1") (pin "GND@3") (pinfunction "GND_GND@3") (pintype "bidirectional"))
    )
    (net (code "110") (name "unconnected-(X1-GND-PadGND@4)") (class "Default")
      (node (ref "X1") (pin "GND@4") (pinfunction "GND_GND@4") (pintype "bidirectional"))
    )
    (net (code "111") (name "unconnected-(X1-GND-PadGND@6)") (class "Default")
      (node (ref "X1") (pin "GND@6") (pinfunction "GND_GND@6") (pintype "bidirectional"))
    )
    (net (code "112") (name "unconnected-(X1-GND-PadGND@7)") (class "Default")
      (node (ref "X1") (pin "GND@7") (pinfunction "GND_GND@7") (pintype "bidirectional"))
    )
    (net (code "113") (name "unconnected-(X1-Pad3V3_EN)") (class "Default")
      (node (ref "X1") (pin "3V3_EN") (pinfunction "3V3_EN_3V3_EN") (pintype "bidirectional"))
    )
    (net (code "114") (name "unconnected-(X1-PadAGND)") (class "Default")
      (node (ref "X1") (pin "AGND") (pinfunction "AGND_AGND") (pintype "bidirectional"))
    )
    (net (code "115") (name "unconnected-(X1-PadGP2)") (class "Default")
      (node (ref "X1") (pin "GP2") (pinfunction "GP2_GP2") (pintype "bidirectional"))
    )
    (net (code "116") (name "unconnected-(X1-PadGP3)") (class "Default")
      (node (ref "X1") (pin "GP3") (pinfunction "GP3_GP3") (pintype "bidirectional"))
    )
    (net (code "117") (name "unconnected-(X1-PadGP7)") (class "Default")
      (node (ref "X1") (pin "GP7") (pinfunction "GP7_GP7") (pintype "bidirectional"))
    )
    (net (code "118") (name "unconnected-(X1-PadGP8)") (class "Default")
      (node (ref "X1") (pin "GP8") (pinfunction "GP8_GP8") (pintype "bidirectional"))
    )
    (net (code "119") (name "unconnected-(X1-PadGP9)") (class "Default")
      (node (ref "X1") (pin "GP9") (pinfunction "GP9_GP9") (pintype "bidirectional"))
    )
    (net (code "120") (name "unconnected-(X1-PadGP10)") (class "Default")
      (node (ref "X1") (pin "GP10") (pinfunction "GP10_GP10") (pintype "bidirectional"))
    )
    (net (code "121") (name "unconnected-(X1-PadGP16)") (class "Default")
      (node (ref "X1") (pin "GP16") (pinfunction "GP16_GP16") (pintype "bidirectional"))
    )
    (net (code "122") (name "unconnected-(X1-PadGP17)") (class "Default")
      (node (ref "X1") (pin "GP17") (pinfunction "GP17_GP17") (pintype "bidirectional"))
    )
    (net (code "123") (name "unconnected-(X1-PadRUN)") (class "Default")
      (node (ref "X1") (pin "RUN") (pinfunction "RUN_RUN") (pintype "bidirectional"))
    )
  )
)
